# GeigerCounter.net
KiCad netlist of a schematic drawn in EAGLE
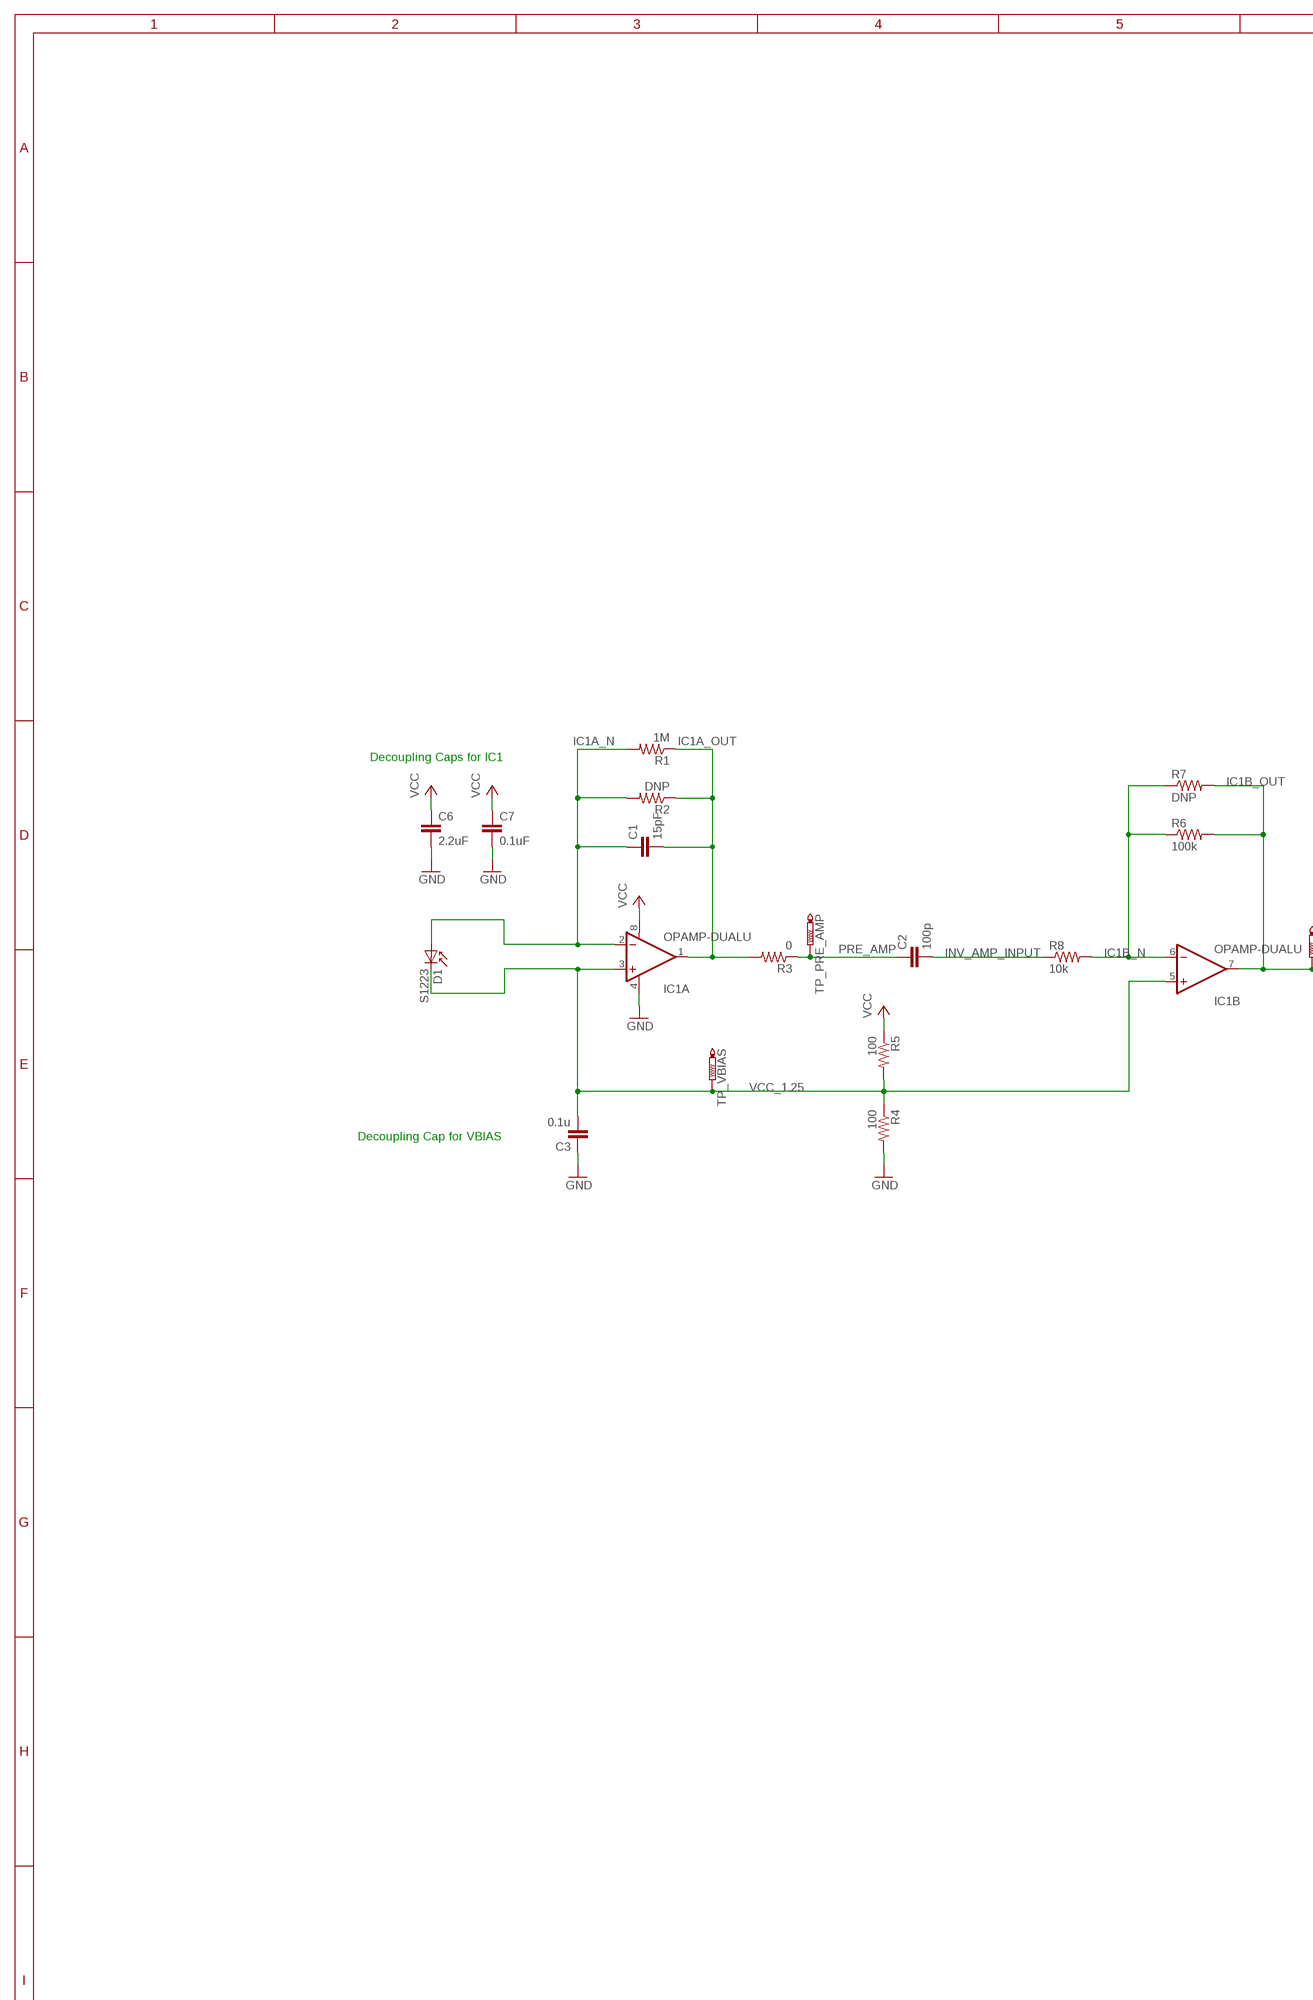
[diagram p0: schematic, sheet 1, part 1 of 2]
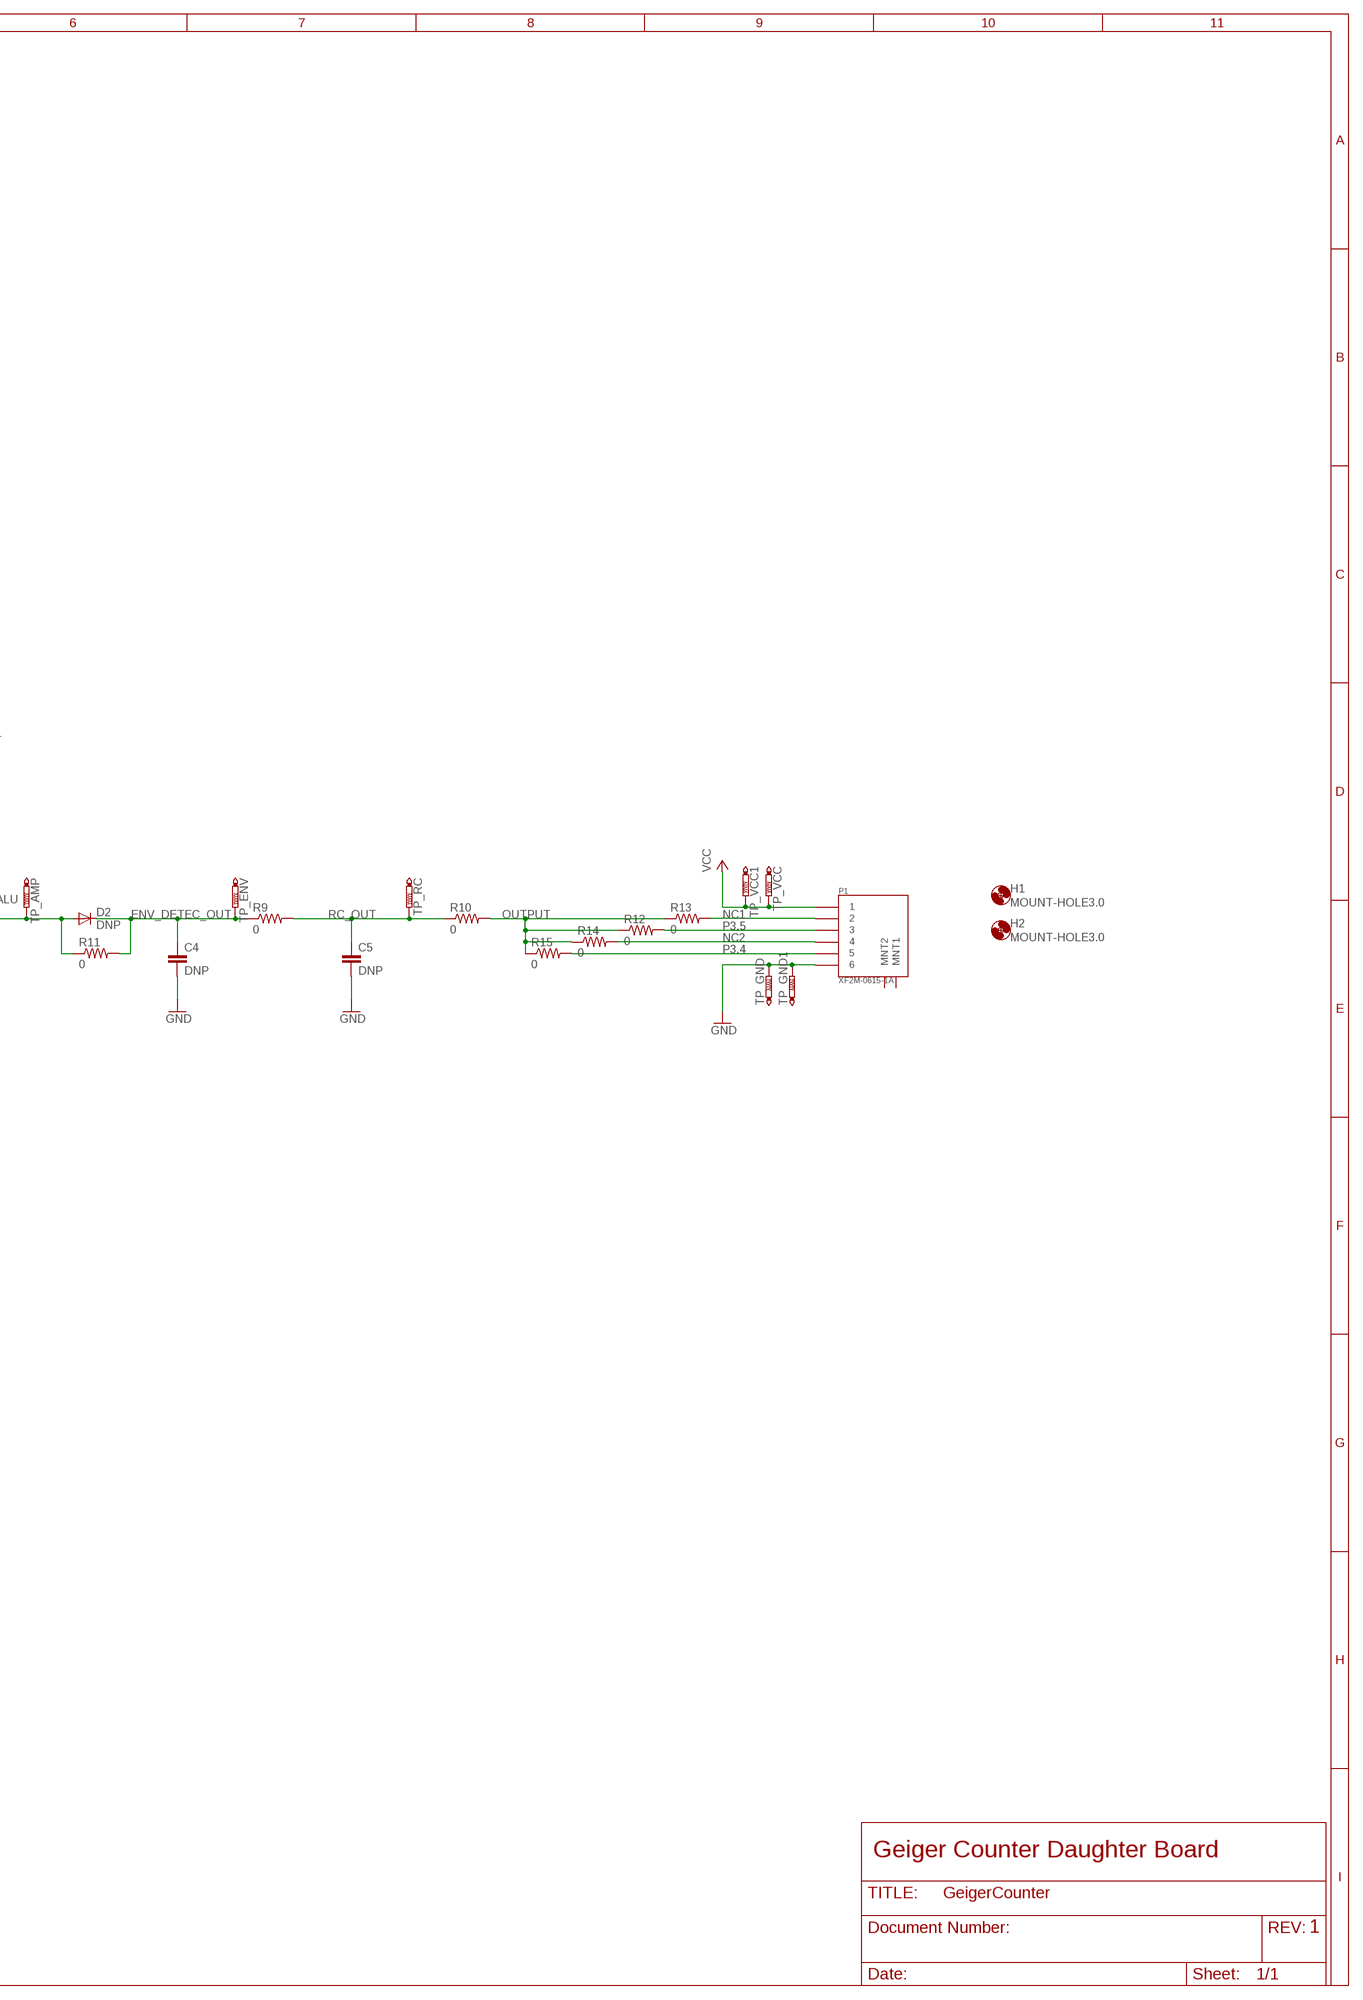
[diagram p1: schematic, sheet 1, part 2 of 2]

(export (version "E")
  (design (tool "Eeschema 10.0.6"))
  (components
    (comp (ref "C1")
      (value "15pF")
      (footprint "eagle-import:0603-CAP")
      (libsource (lib "eagle-import") (part "CAP0603-CAP"))
    )
    (comp (ref "C2")
      (value "100p")
      (footprint "eagle-import:0603-CAP")
      (libsource (lib "eagle-import") (part "CAP0603-CAP"))
    )
    (comp (ref "C3")
      (value "0.1u")
      (footprint "eagle-import:0603-CAP")
      (libsource (lib "eagle-import") (part "CAP0603-CAP"))
    )
    (comp (ref "C4")
      (value "DNP")
      (footprint "eagle-import:0603-CAP")
      (libsource (lib "eagle-import") (part "CAP0603-CAP"))
    )
    (comp (ref "C5")
      (value "DNP")
      (footprint "eagle-import:0603-CAP")
      (libsource (lib "eagle-import") (part "CAP0603-CAP"))
    )
    (comp (ref "C6")
      (value "2.2uF")
      (footprint "eagle-import:0603-CAP")
      (libsource (lib "eagle-import") (part "CAP0603-CAP"))
    )
    (comp (ref "C7")
      (value "0.1uF")
      (footprint "eagle-import:0603-CAP")
      (libsource (lib "eagle-import") (part "CAP0603-CAP"))
    )
    (comp (ref "D1")
      (value "S1223")
      (footprint "eagle-import:DIODE-1N4001")
      (libsource (lib "eagle-import") (part "S1223"))
    )
    (comp (ref "D2")
      (value "DNP")
      (footprint "eagle-import:SOT23-3")
      (libsource (lib "eagle-import") (part "DIODESOT23"))
    )
    (comp (ref "H1")
      (value "MOUNT-HOLE3.0")
      (footprint "eagle-import:3,0")
      (libsource (lib "eagle-import") (part "MOUNT-HOLE3.0"))
    )
    (comp (ref "H2")
      (value "MOUNT-HOLE3.0")
      (footprint "eagle-import:3,0")
      (libsource (lib "eagle-import") (part "MOUNT-HOLE3.0"))
    )
    (comp (ref "IC1")
      (value "OPAMP-DUALU")
      (footprint "eagle-import:SO08")
      (libsource (lib "eagle-import") (part "OPAMP-DUALU"))
    )
    (comp (ref "P1")
      (value "XF2M-0615-1A")
      (footprint "eagle-import:XF2M-0615-1A")
      (libsource (lib "eagle-import") (part "XF2M-0615-1A"))
    )
    (comp (ref "R1")
      (value "1M")
      (footprint "eagle-import:0603-RES")
      (libsource (lib "eagle-import") (part "RESISTOR0603-RES"))
    )
    (comp (ref "R2")
      (value "DNP")
      (footprint "eagle-import:0603-RES")
      (libsource (lib "eagle-import") (part "RESISTOR0603-RES"))
    )
    (comp (ref "R3")
      (value "0")
      (footprint "eagle-import:0603-RES")
      (libsource (lib "eagle-import") (part "RESISTOR0603-RES"))
    )
    (comp (ref "R4")
      (value "100")
      (footprint "eagle-import:0603-RES")
      (libsource (lib "eagle-import") (part "RESISTOR0603-RES"))
    )
    (comp (ref "R5")
      (value "100")
      (footprint "eagle-import:0603-RES")
      (libsource (lib "eagle-import") (part "RESISTOR0603-RES"))
    )
    (comp (ref "R6")
      (value "100k")
      (footprint "eagle-import:0603-RES")
      (libsource (lib "eagle-import") (part "RESISTOR0603-RES"))
    )
    (comp (ref "R7")
      (value "DNP")
      (footprint "eagle-import:0603-RES")
      (libsource (lib "eagle-import") (part "RESISTOR0603-RES"))
    )
    (comp (ref "R8")
      (value "10k")
      (footprint "eagle-import:0603-RES")
      (libsource (lib "eagle-import") (part "RESISTOR0603-RES"))
    )
    (comp (ref "R9")
      (value "0")
      (footprint "eagle-import:0603-RES")
      (libsource (lib "eagle-import") (part "RESISTOR0603-RES"))
    )
    (comp (ref "R10")
      (value "0")
      (footprint "eagle-import:0603-RES")
      (libsource (lib "eagle-import") (part "RESISTOR0603-RES"))
    )
    (comp (ref "R11")
      (value "0")
      (footprint "eagle-import:0603-RES")
      (libsource (lib "eagle-import") (part "RESISTOR0603-RES"))
    )
    (comp (ref "R12")
      (value "0")
      (footprint "eagle-import:0603-RES")
      (libsource (lib "eagle-import") (part "RESISTOR0603-RES"))
    )
    (comp (ref "R13")
      (value "0")
      (footprint "eagle-import:0603-RES")
      (libsource (lib "eagle-import") (part "RESISTOR0603-RES"))
    )
    (comp (ref "R14")
      (value "0")
      (footprint "eagle-import:0603-RES")
      (libsource (lib "eagle-import") (part "RESISTOR0603-RES"))
    )
    (comp (ref "R15")
      (value "0")
      (footprint "eagle-import:0603-RES")
      (libsource (lib "eagle-import") (part "RESISTOR0603-RES"))
    )
    (comp (ref "TP_AMP")
      (value "PTR1PAD1-20")
      (footprint "eagle-import:P1-20")
      (libsource (lib "eagle-import") (part "PTR1PAD1-20"))
    )
    (comp (ref "TP_ENV")
      (value "PTR1PAD1-20")
      (footprint "eagle-import:P1-20")
      (libsource (lib "eagle-import") (part "PTR1PAD1-20"))
    )
    (comp (ref "TP_GND")
      (value "PTR1PAD1-20")
      (footprint "eagle-import:P1-20")
      (libsource (lib "eagle-import") (part "PTR1PAD1-20"))
    )
    (comp (ref "TP_GND1")
      (value "PTR1PAD1-20")
      (footprint "eagle-import:P1-20")
      (libsource (lib "eagle-import") (part "PTR1PAD1-20"))
    )
    (comp (ref "TP_PRE_AMP")
      (value "PTR1PAD1-20")
      (footprint "eagle-import:P1-20")
      (libsource (lib "eagle-import") (part "PTR1PAD1-20"))
    )
    (comp (ref "TP_RC")
      (value "PTR1PAD1-20")
      (footprint "eagle-import:P1-20")
      (libsource (lib "eagle-import") (part "PTR1PAD1-20"))
    )
    (comp (ref "TP_VBIAS")
      (value "PTR1PAD1-20")
      (footprint "eagle-import:P1-20")
      (libsource (lib "eagle-import") (part "PTR1PAD1-20"))
    )
    (comp (ref "TP_VCC")
      (value "PTR1PAD1-20")
      (footprint "eagle-import:P1-20")
      (libsource (lib "eagle-import") (part "PTR1PAD1-20"))
    )
    (comp (ref "TP_VCC1")
      (value "PTR1PAD1-20")
      (footprint "eagle-import:P1-20")
      (libsource (lib "eagle-import") (part "PTR1PAD1-20"))
    )
  )
  (nets
    (net (code "1") (name "/ENV_DETEC_OUT") (class "Default")
      (node (ref "C4") (pin "1") (pinfunction "1_1") (pintype "passive"))
      (node (ref "D2") (pin "3") (pinfunction "C_3") (pintype "passive"))
      (node (ref "R11") (pin "2") (pinfunction "2_2") (pintype "passive"))
      (node (ref "R9") (pin "1") (pinfunction "1_1") (pintype "passive"))
      (node (ref "TP_ENV") (pin "TP") (pinfunction "TP_TP") (pintype "input"))
    )
    (net (code "2") (name "/IC1A_N") (class "Default")
      (node (ref "C1") (pin "1") (pinfunction "1_1") (pintype "passive"))
      (node (ref "D1") (pin "A") (pinfunction "A_A") (pintype "passive"))
      (node (ref "IC1") (pin "2") (pinfunction "-IN_2") (pintype "input"))
      (node (ref "R1") (pin "2") (pinfunction "2_2") (pintype "passive"))
      (node (ref "R2") (pin "2") (pinfunction "2_2") (pintype "passive"))
    )
    (net (code "3") (name "/IC1A_OUT") (class "Default")
      (node (ref "C1") (pin "2") (pinfunction "2_2") (pintype "passive"))
      (node (ref "IC1") (pin "1") (pinfunction "OUT_1") (pintype "output"))
      (node (ref "R1") (pin "1") (pinfunction "1_1") (pintype "passive"))
      (node (ref "R2") (pin "1") (pinfunction "1_1") (pintype "passive"))
      (node (ref "R3") (pin "2") (pinfunction "2_2") (pintype "passive"))
    )
    (net (code "4") (name "/IC1B_N") (class "Default")
      (node (ref "IC1") (pin "6") (pinfunction "-IN_6") (pintype "input"))
      (node (ref "R6") (pin "1") (pinfunction "1_1") (pintype "passive"))
      (node (ref "R7") (pin "1") (pinfunction "1_1") (pintype "passive"))
      (node (ref "R8") (pin "2") (pinfunction "2_2") (pintype "passive"))
    )
    (net (code "5") (name "/IC1B_OUT") (class "Default")
      (node (ref "D2") (pin "1") (pinfunction "A_1") (pintype "passive"))
      (node (ref "IC1") (pin "7") (pinfunction "OUT_7") (pintype "output"))
      (node (ref "R11") (pin "1") (pinfunction "1_1") (pintype "passive"))
      (node (ref "R6") (pin "2") (pinfunction "2_2") (pintype "passive"))
      (node (ref "R7") (pin "2") (pinfunction "2_2") (pintype "passive"))
      (node (ref "TP_AMP") (pin "TP") (pinfunction "TP_TP") (pintype "input"))
    )
    (net (code "6") (name "/INV_AMP_INPUT") (class "Default")
      (node (ref "C2") (pin "2") (pinfunction "2_2") (pintype "passive"))
      (node (ref "R8") (pin "1") (pinfunction "1_1") (pintype "passive"))
    )
    (net (code "7") (name "/NC1") (class "Default")
      (node (ref "P1") (pin "2") (pinfunction "2_2") (pintype "bidirectional"))
      (node (ref "R13") (pin "2") (pinfunction "2_2") (pintype "passive"))
    )
    (net (code "8") (name "/NC2") (class "Default")
      (node (ref "P1") (pin "4") (pinfunction "4_4") (pintype "bidirectional"))
      (node (ref "R14") (pin "2") (pinfunction "2_2") (pintype "passive"))
    )
    (net (code "9") (name "/OUTPUT") (class "Default")
      (node (ref "R10") (pin "2") (pinfunction "2_2") (pintype "passive"))
      (node (ref "R12") (pin "1") (pinfunction "1_1") (pintype "passive"))
      (node (ref "R13") (pin "1") (pinfunction "1_1") (pintype "passive"))
      (node (ref "R14") (pin "1") (pinfunction "1_1") (pintype "passive"))
      (node (ref "R15") (pin "1") (pinfunction "1_1") (pintype "passive"))
    )
    (net (code "10") (name "/P3.4") (class "Default")
      (node (ref "P1") (pin "5") (pinfunction "5_5") (pintype "bidirectional"))
      (node (ref "R15") (pin "2") (pinfunction "2_2") (pintype "passive"))
    )
    (net (code "11") (name "/P3.5") (class "Default")
      (node (ref "P1") (pin "3") (pinfunction "3_3") (pintype "bidirectional"))
      (node (ref "R12") (pin "2") (pinfunction "2_2") (pintype "passive"))
    )
    (net (code "12") (name "/PRE_AMP") (class "Default")
      (node (ref "C2") (pin "1") (pinfunction "1_1") (pintype "passive"))
      (node (ref "R3") (pin "1") (pinfunction "1_1") (pintype "passive"))
      (node (ref "TP_PRE_AMP") (pin "TP") (pinfunction "TP_TP") (pintype "input"))
    )
    (net (code "13") (name "/RC_OUT") (class "Default")
      (node (ref "C5") (pin "1") (pinfunction "1_1") (pintype "passive"))
      (node (ref "R10") (pin "1") (pinfunction "1_1") (pintype "passive"))
      (node (ref "R9") (pin "2") (pinfunction "2_2") (pintype "passive"))
      (node (ref "TP_RC") (pin "TP") (pinfunction "TP_TP") (pintype "input"))
    )
    (net (code "14") (name "/VCC_1.25") (class "Default")
      (node (ref "C3") (pin "2") (pinfunction "2_2") (pintype "passive"))
      (node (ref "D1") (pin "C") (pinfunction "C_C") (pintype "passive"))
      (node (ref "IC1") (pin "3") (pinfunction "+IN_3") (pintype "input"))
      (node (ref "IC1") (pin "5") (pinfunction "+IN_5") (pintype "input"))
      (node (ref "R4") (pin "1") (pinfunction "1_1") (pintype "passive"))
      (node (ref "R5") (pin "2") (pinfunction "2_2") (pintype "passive"))
      (node (ref "TP_VBIAS") (pin "TP") (pinfunction "TP_TP") (pintype "input"))
    )
    (net (code "15") (name "GND") (class "Default")
      (node (ref "C3") (pin "1") (pinfunction "1_1") (pintype "passive"))
      (node (ref "C4") (pin "2") (pinfunction "2_2") (pintype "passive"))
      (node (ref "C5") (pin "2") (pinfunction "2_2") (pintype "passive"))
      (node (ref "C6") (pin "2") (pinfunction "2_2") (pintype "passive"))
      (node (ref "C7") (pin "2") (pinfunction "2_2") (pintype "passive"))
      (node (ref "IC1") (pin "4") (pinfunction "V-_4") (pintype "power_in"))
      (node (ref "P1") (pin "6") (pinfunction "6_6") (pintype "bidirectional"))
      (node (ref "R4") (pin "2") (pinfunction "2_2") (pintype "passive"))
      (node (ref "TP_GND") (pin "TP") (pinfunction "TP_TP") (pintype "input"))
      (node (ref "TP_GND1") (pin "TP") (pinfunction "TP_TP") (pintype "input"))
    )
    (net (code "16") (name "VCC") (class "Default")
      (node (ref "C6") (pin "1") (pinfunction "1_1") (pintype "passive"))
      (node (ref "C7") (pin "1") (pinfunction "1_1") (pintype "passive"))
      (node (ref "IC1") (pin "8") (pinfunction "V+_8") (pintype "power_in"))
      (node (ref "P1") (pin "1") (pinfunction "1_1") (pintype "bidirectional"))
      (node (ref "R5") (pin "1") (pinfunction "1_1") (pintype "passive"))
      (node (ref "TP_VCC") (pin "TP") (pinfunction "TP_TP") (pintype "input"))
      (node (ref "TP_VCC1") (pin "TP") (pinfunction "TP_TP") (pintype "input"))
    )
    (net (code "17") (name "unconnected-(P1-MNT1-PadP$7)") (class "Default")
      (node (ref "P1") (pin "P$7") (pinfunction "MNT1_P$7") (pintype "no_connect"))
    )
    (net (code "18") (name "unconnected-(P1-MNT2-PadP$8)") (class "Default")
      (node (ref "P1") (pin "P$8") (pinfunction "MNT2_P$8") (pintype "no_connect"))
    )
  )
)
